# laserbox-muxboard.net
KiCad netlist of a schematic drawn in EAGLE
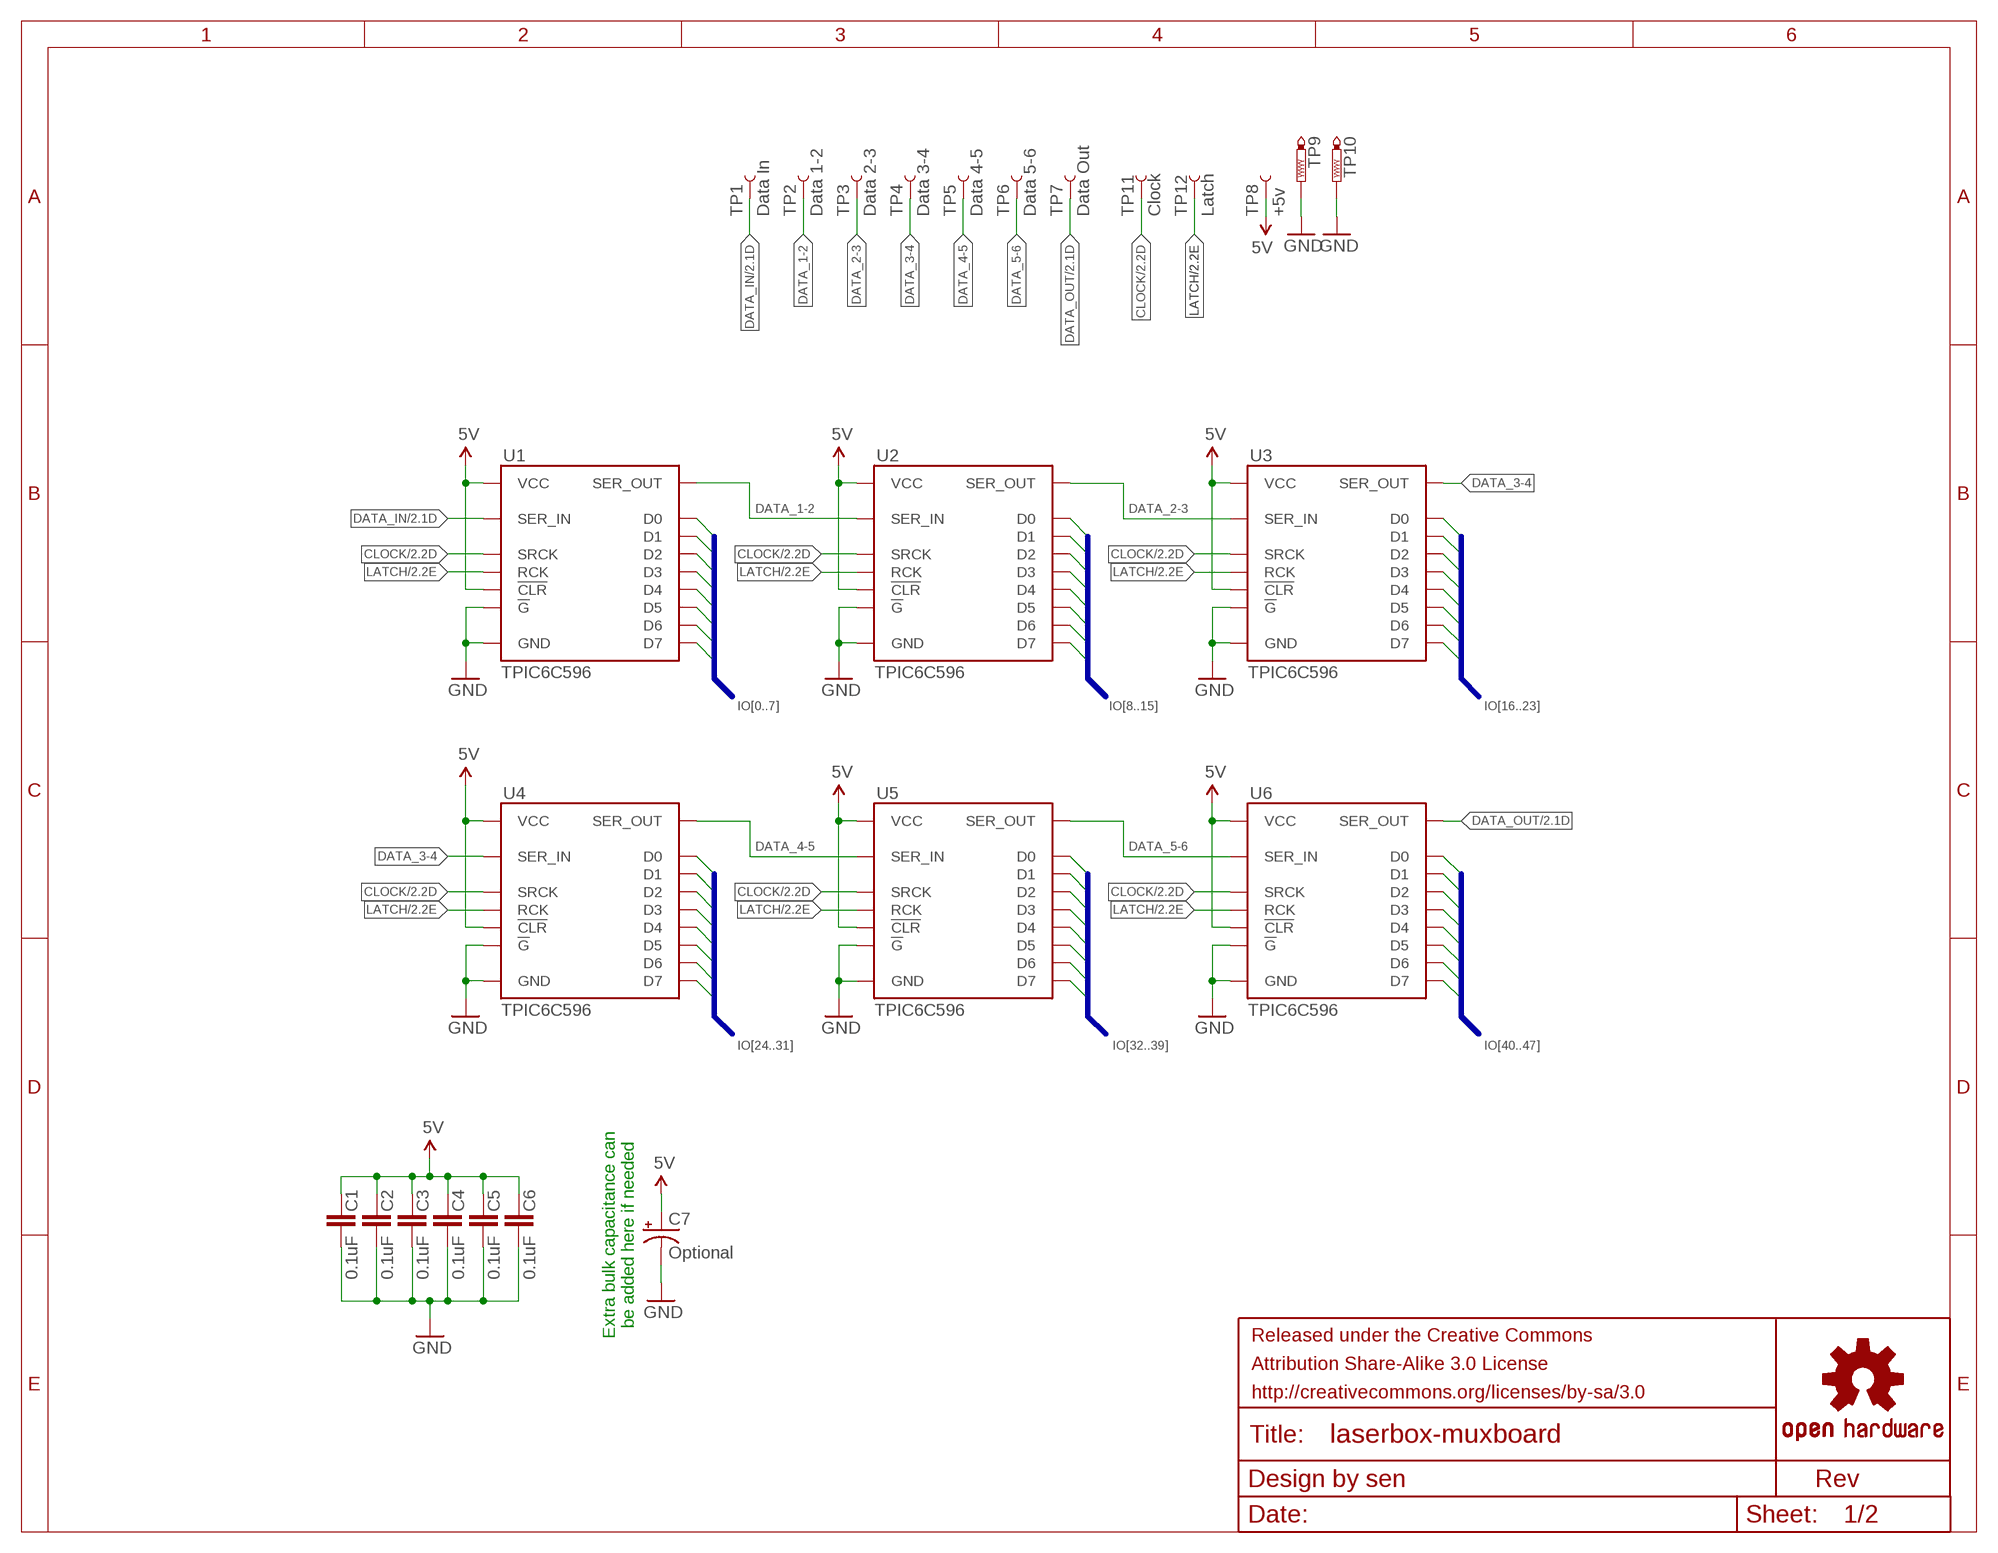
[diagram p0: schematic, sheet 1]
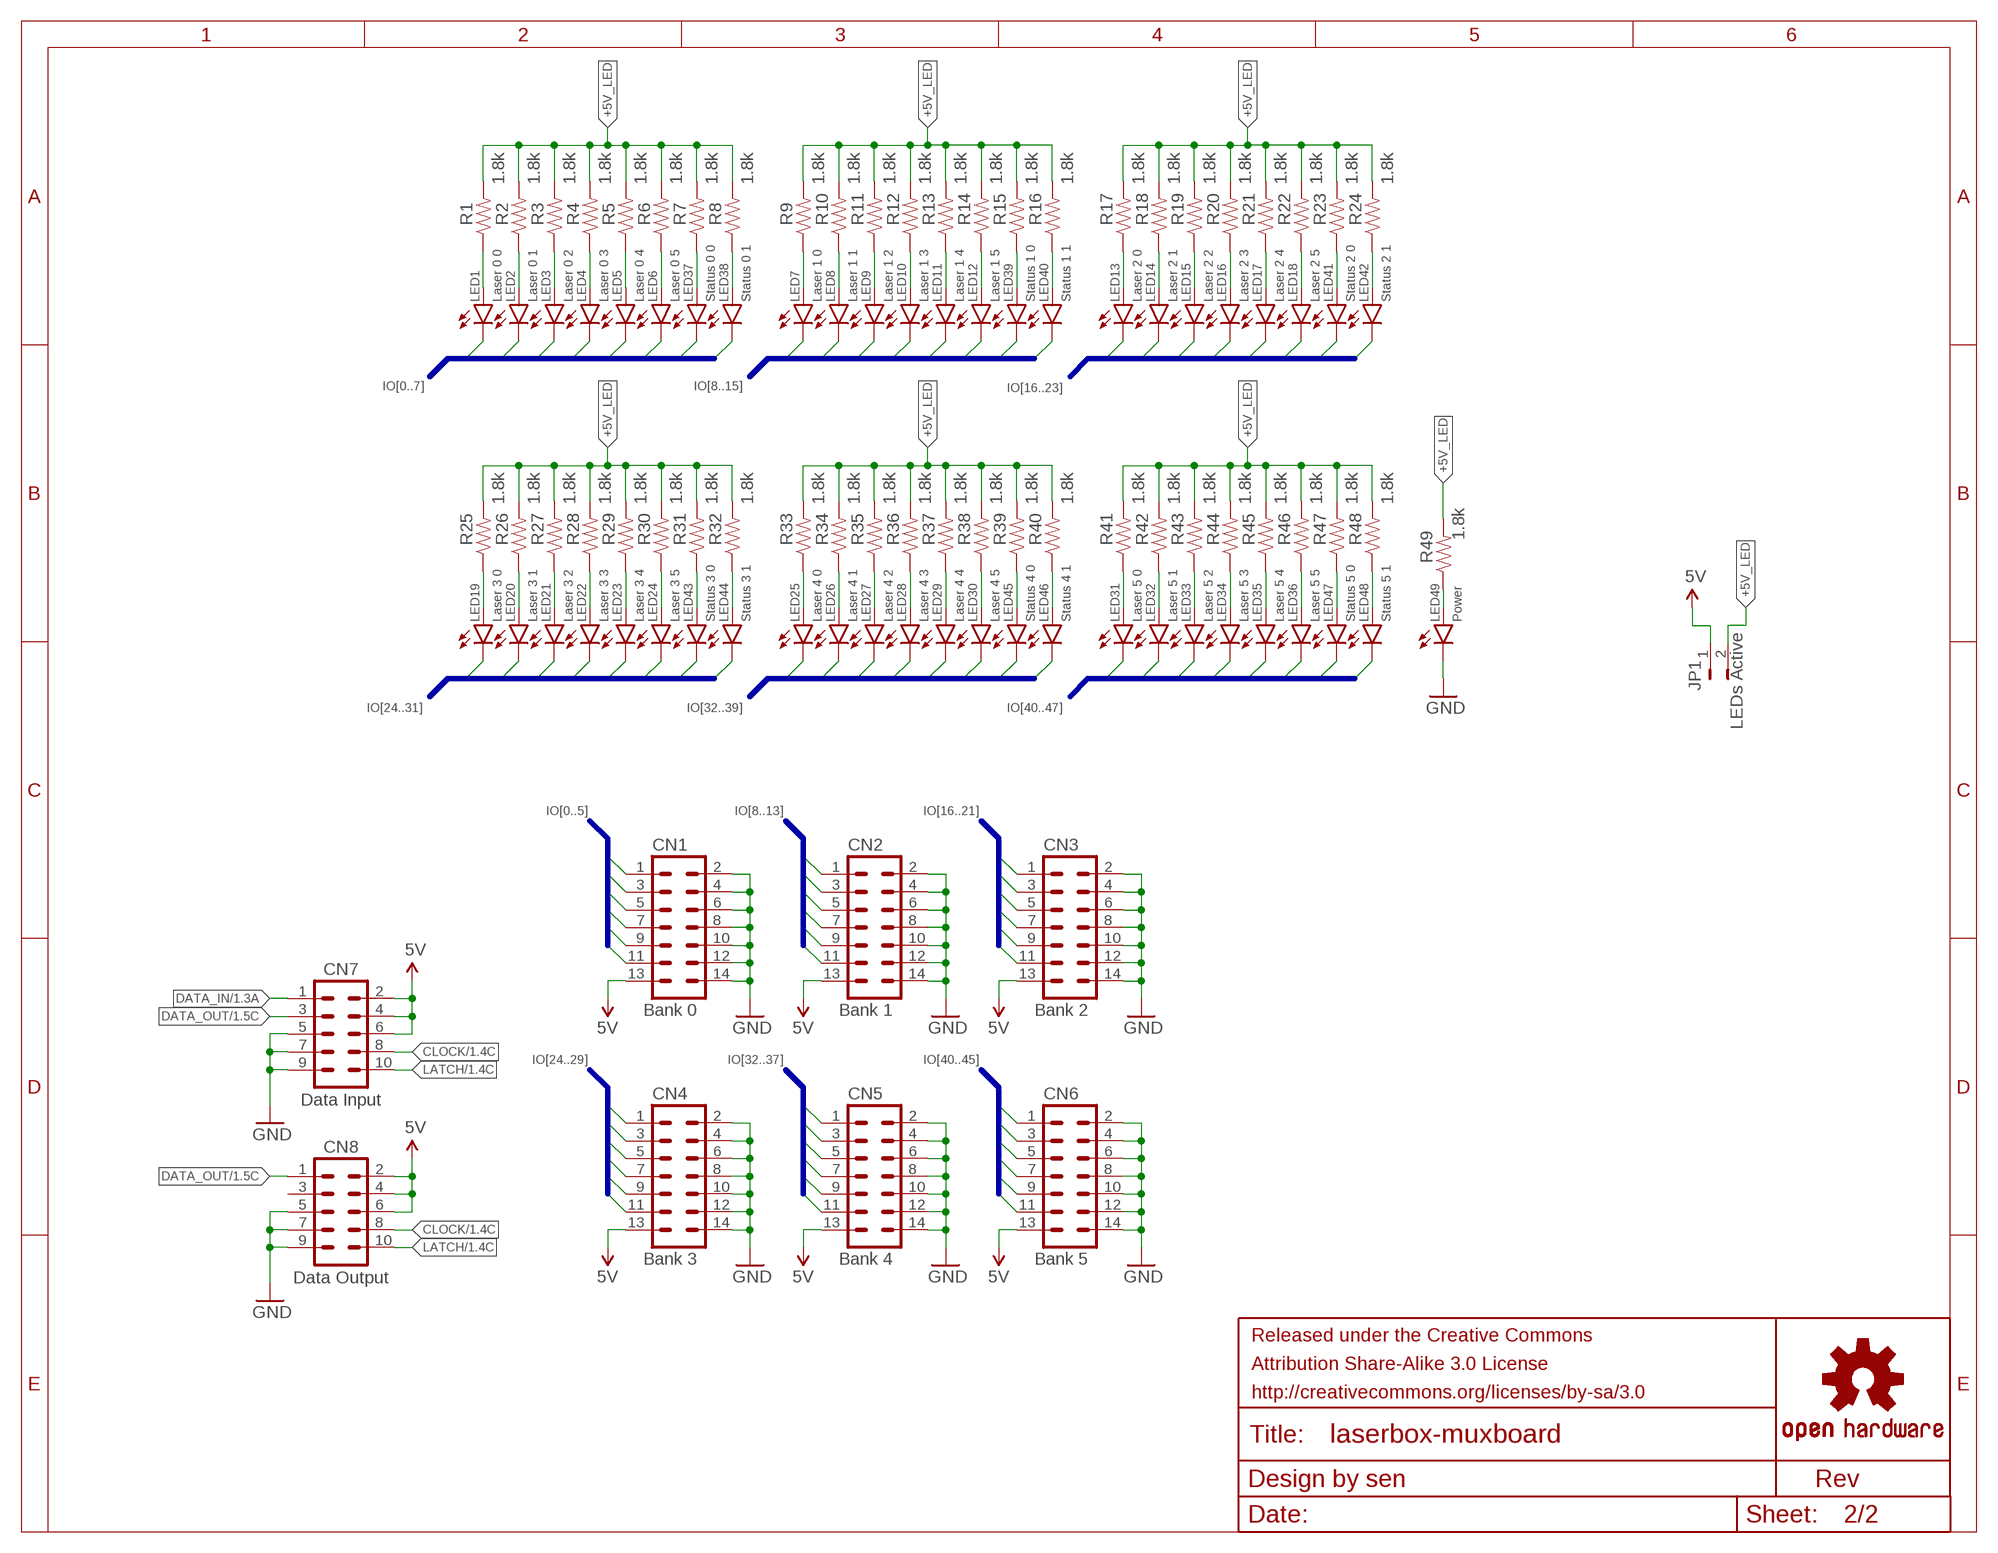
[diagram p1: schematic, sheet 2]

(export (version "E")
  (design (tool "Eeschema 10.0.6"))
  (components
    (comp (ref "C1")
      (value "0.1uF")
      (footprint "eagle-import:0603-CAP")
      (libsource (lib "eagle-import") (part "0.1UF-25V-5%(0603)"))
    )
    (comp (ref "C2")
      (value "0.1uF")
      (footprint "eagle-import:0603-CAP")
      (libsource (lib "eagle-import") (part "0.1UF-25V-5%(0603)"))
    )
    (comp (ref "C3")
      (value "0.1uF")
      (footprint "eagle-import:0603-CAP")
      (libsource (lib "eagle-import") (part "0.1UF-25V-5%(0603)"))
    )
    (comp (ref "C4")
      (value "0.1uF")
      (footprint "eagle-import:0603-CAP")
      (libsource (lib "eagle-import") (part "0.1UF-25V-5%(0603)"))
    )
    (comp (ref "C5")
      (value "0.1uF")
      (footprint "eagle-import:0603-CAP")
      (libsource (lib "eagle-import") (part "0.1UF-25V-5%(0603)"))
    )
    (comp (ref "C6")
      (value "0.1uF")
      (footprint "eagle-import:0603-CAP")
      (libsource (lib "eagle-import") (part "0.1UF-25V-5%(0603)"))
    )
    (comp (ref "C7")
      (value "Optional")
      (footprint "eagle-import:CPOL-RADIAL-10UF-25V")
      (libsource (lib "eagle-import") (part "CAP_POLPTH2"))
    )
    (comp (ref "FRAME1")
      (value "FRAME-LETTER-GRID-OSHW-SENOSHW-LOGO-L")
      (footprint "eagle-import:OSHW-LOGO-L")
      (fields (field (name "REV") "001"))
      (libsource (lib "eagle-import") (part "FRAME-LETTER-GRID-OSHW-SENOSHW-LOGO-L"))
    )
    (comp (ref "TP1")
      (value "Data In")
      (footprint "eagle-import:PAD.03X.05")
      (libsource (lib "eagle-import") (part "TEST-POINT3X5"))
    )
    (comp (ref "TP2")
      (value "Data 1-2")
      (footprint "eagle-import:PAD.03X.05")
      (libsource (lib "eagle-import") (part "TEST-POINT3X5"))
    )
    (comp (ref "TP3")
      (value "Data 2-3")
      (footprint "eagle-import:PAD.03X.05")
      (libsource (lib "eagle-import") (part "TEST-POINT3X5"))
    )
    (comp (ref "TP4")
      (value "Data 3-4")
      (footprint "eagle-import:PAD.03X.05")
      (libsource (lib "eagle-import") (part "TEST-POINT3X5"))
    )
    (comp (ref "TP5")
      (value "Data 4-5")
      (footprint "eagle-import:PAD.03X.05")
      (libsource (lib "eagle-import") (part "TEST-POINT3X5"))
    )
    (comp (ref "TP6")
      (value "Data 5-6")
      (footprint "eagle-import:PAD.03X.05")
      (libsource (lib "eagle-import") (part "TEST-POINT3X5"))
    )
    (comp (ref "TP7")
      (value "Data Out")
      (footprint "eagle-import:PAD.03X.05")
      (libsource (lib "eagle-import") (part "TEST-POINT3X5"))
    )
    (comp (ref "TP8")
      (value "+5v")
      (footprint "eagle-import:PAD.03X.05")
      (libsource (lib "eagle-import") (part "TEST-POINT3X5"))
    )
    (comp (ref "TP9")
      (value "GND")
      (footprint "eagle-import:P1-13")
      (libsource (lib "eagle-import") (part "PTR1PAD1-13"))
    )
    (comp (ref "TP10")
      (value "GND")
      (footprint "eagle-import:P1-13")
      (libsource (lib "eagle-import") (part "PTR1PAD1-13"))
    )
    (comp (ref "TP11")
      (value "Clock")
      (footprint "eagle-import:PAD.03X.05")
      (libsource (lib "eagle-import") (part "TEST-POINT3X5"))
    )
    (comp (ref "TP12")
      (value "Latch")
      (footprint "eagle-import:PAD.03X.05")
      (libsource (lib "eagle-import") (part "TEST-POINT3X5"))
    )
    (comp (ref "U1")
      (value "TPIC6C596")
      (footprint "eagle-import:SO016")
      (libsource (lib "eagle-import") (part "TPIC6C596SOIC"))
    )
    (comp (ref "U2")
      (value "TPIC6C596")
      (footprint "eagle-import:SO016")
      (libsource (lib "eagle-import") (part "TPIC6C596SOIC"))
    )
    (comp (ref "U3")
      (value "TPIC6C596")
      (footprint "eagle-import:SO016")
      (libsource (lib "eagle-import") (part "TPIC6C596SOIC"))
    )
    (comp (ref "U4")
      (value "TPIC6C596")
      (footprint "eagle-import:SO016")
      (libsource (lib "eagle-import") (part "TPIC6C596SOIC"))
    )
    (comp (ref "U5")
      (value "TPIC6C596")
      (footprint "eagle-import:SO016")
      (libsource (lib "eagle-import") (part "TPIC6C596SOIC"))
    )
    (comp (ref "U6")
      (value "TPIC6C596")
      (footprint "eagle-import:SO016")
      (libsource (lib "eagle-import") (part "TPIC6C596SOIC"))
    )
    (comp (ref "CN1")
      (value "Bank 0")
      (footprint "eagle-import:2X7-SHROUDED_LOCK")
      (libsource (lib "eagle-import") (part "M07X2"))
    )
    (comp (ref "CN2")
      (value "Bank 1")
      (footprint "eagle-import:2X7-SHROUDED_LOCK")
      (libsource (lib "eagle-import") (part "M07X2"))
    )
    (comp (ref "CN3")
      (value "Bank 2")
      (footprint "eagle-import:2X7-SHROUDED_LOCK")
      (libsource (lib "eagle-import") (part "M07X2"))
    )
    (comp (ref "CN4")
      (value "Bank 3")
      (footprint "eagle-import:2X7-SHROUDED_LOCK")
      (libsource (lib "eagle-import") (part "M07X2"))
    )
    (comp (ref "CN5")
      (value "Bank 4")
      (footprint "eagle-import:2X7-SHROUDED_LOCK")
      (libsource (lib "eagle-import") (part "M07X2"))
    )
    (comp (ref "CN6")
      (value "Bank 5")
      (footprint "eagle-import:2X7-SHROUDED_LOCK")
      (libsource (lib "eagle-import") (part "M07X2"))
    )
    (comp (ref "CN7")
      (value "Data Input")
      (footprint "eagle-import:2X5-SHROUDED_LOCK")
      (libsource (lib "eagle-import") (part "M05X2SHD_LOCK"))
    )
    (comp (ref "CN8")
      (value "Data Output")
      (footprint "eagle-import:2X5-SHROUDED_LOCK")
      (libsource (lib "eagle-import") (part "M05X2SHD_LOCK"))
    )
    (comp (ref "FRAME2")
      (value "FRAME-LETTER-GRID-OSHW-SENOSHW-LOGO-L")
      (footprint "eagle-import:OSHW-LOGO-L")
      (fields (field (name "REV") "001"))
      (libsource (lib "eagle-import") (part "FRAME-LETTER-GRID-OSHW-SENOSHW-LOGO-L"))
    )
    (comp (ref "JP1")
      (value "LEDs Active")
      (footprint "eagle-import:PTH-JUMPER-2-NO_NO_SILK")
      (libsource (lib "eagle-import") (part "JUMPER-PTH-2-NO"))
    )
    (comp (ref "LED1")
      (value "Laser 0 0")
      (footprint "eagle-import:LED3MM")
      (libsource (lib "eagle-import") (part "LED3MM"))
    )
    (comp (ref "LED2")
      (value "Laser 0 1")
      (footprint "eagle-import:LED3MM")
      (libsource (lib "eagle-import") (part "LED3MM"))
    )
    (comp (ref "LED3")
      (value "Laser 0 2")
      (footprint "eagle-import:LED3MM")
      (libsource (lib "eagle-import") (part "LED3MM"))
    )
    (comp (ref "LED4")
      (value "Laser 0 3")
      (footprint "eagle-import:LED3MM")
      (libsource (lib "eagle-import") (part "LED3MM"))
    )
    (comp (ref "LED5")
      (value "Laser 0 4")
      (footprint "eagle-import:LED3MM")
      (libsource (lib "eagle-import") (part "LED3MM"))
    )
    (comp (ref "LED6")
      (value "Laser 0 5")
      (footprint "eagle-import:LED3MM")
      (libsource (lib "eagle-import") (part "LED3MM"))
    )
    (comp (ref "LED7")
      (value "Laser 1 0")
      (footprint "eagle-import:LED3MM")
      (libsource (lib "eagle-import") (part "LED3MM"))
    )
    (comp (ref "LED8")
      (value "Laser 1 1")
      (footprint "eagle-import:LED3MM")
      (libsource (lib "eagle-import") (part "LED3MM"))
    )
    (comp (ref "LED9")
      (value "Laser 1 2")
      (footprint "eagle-import:LED3MM")
      (libsource (lib "eagle-import") (part "LED3MM"))
    )
    (comp (ref "LED10")
      (value "Laser 1 3")
      (footprint "eagle-import:LED3MM")
      (libsource (lib "eagle-import") (part "LED3MM"))
    )
    (comp (ref "LED11")
      (value "Laser 1 4")
      (footprint "eagle-import:LED3MM")
      (libsource (lib "eagle-import") (part "LED3MM"))
    )
    (comp (ref "LED12")
      (value "Laser 1 5")
      (footprint "eagle-import:LED3MM")
      (libsource (lib "eagle-import") (part "LED3MM"))
    )
    (comp (ref "LED13")
      (value "Laser 2 0")
      (footprint "eagle-import:LED3MM")
      (libsource (lib "eagle-import") (part "LED3MM"))
    )
    (comp (ref "LED14")
      (value "Laser 2 1")
      (footprint "eagle-import:LED3MM")
      (libsource (lib "eagle-import") (part "LED3MM"))
    )
    (comp (ref "LED15")
      (value "Laser 2 2")
      (footprint "eagle-import:LED3MM")
      (libsource (lib "eagle-import") (part "LED3MM"))
    )
    (comp (ref "LED16")
      (value "Laser 2 3")
      (footprint "eagle-import:LED3MM")
      (libsource (lib "eagle-import") (part "LED3MM"))
    )
    (comp (ref "LED17")
      (value "Laser 2 4")
      (footprint "eagle-import:LED3MM")
      (libsource (lib "eagle-import") (part "LED3MM"))
    )
    (comp (ref "LED18")
      (value "Laser 2 5")
      (footprint "eagle-import:LED3MM")
      (libsource (lib "eagle-import") (part "LED3MM"))
    )
    (comp (ref "LED19")
      (value "Laser 3 0")
      (footprint "eagle-import:LED3MM")
      (libsource (lib "eagle-import") (part "LED3MM"))
    )
    (comp (ref "LED20")
      (value "Laser 3 1")
      (footprint "eagle-import:LED3MM")
      (libsource (lib "eagle-import") (part "LED3MM"))
    )
    (comp (ref "LED21")
      (value "Laser 3 2")
      (footprint "eagle-import:LED3MM")
      (libsource (lib "eagle-import") (part "LED3MM"))
    )
    (comp (ref "LED22")
      (value "Laser 3 3")
      (footprint "eagle-import:LED3MM")
      (libsource (lib "eagle-import") (part "LED3MM"))
    )
    (comp (ref "LED23")
      (value "Laser 3 4")
      (footprint "eagle-import:LED3MM")
      (libsource (lib "eagle-import") (part "LED3MM"))
    )
    (comp (ref "LED24")
      (value "Laser 3 5")
      (footprint "eagle-import:LED3MM")
      (libsource (lib "eagle-import") (part "LED3MM"))
    )
    (comp (ref "LED25")
      (value "Laser 4 0")
      (footprint "eagle-import:LED3MM")
      (libsource (lib "eagle-import") (part "LED3MM"))
    )
    (comp (ref "LED26")
      (value "Laser 4 1")
      (footprint "eagle-import:LED3MM")
      (libsource (lib "eagle-import") (part "LED3MM"))
    )
    (comp (ref "LED27")
      (value "Laser 4 2")
      (footprint "eagle-import:LED3MM")
      (libsource (lib "eagle-import") (part "LED3MM"))
    )
    (comp (ref "LED28")
      (value "Laser 4 3")
      (footprint "eagle-import:LED3MM")
      (libsource (lib "eagle-import") (part "LED3MM"))
    )
    (comp (ref "LED29")
      (value "Laser 4 4")
      (footprint "eagle-import:LED3MM")
      (libsource (lib "eagle-import") (part "LED3MM"))
    )
    (comp (ref "LED30")
      (value "Laser 4 5")
      (footprint "eagle-import:LED3MM")
      (libsource (lib "eagle-import") (part "LED3MM"))
    )
    (comp (ref "LED31")
      (value "Laser 5 0")
      (footprint "eagle-import:LED3MM")
      (libsource (lib "eagle-import") (part "LED3MM"))
    )
    (comp (ref "LED32")
      (value "Laser 5 1")
      (footprint "eagle-import:LED3MM")
      (libsource (lib "eagle-import") (part "LED3MM"))
    )
    (comp (ref "LED33")
      (value "Laser 5 2")
      (footprint "eagle-import:LED3MM")
      (libsource (lib "eagle-import") (part "LED3MM"))
    )
    (comp (ref "LED34")
      (value "Laser 5 3")
      (footprint "eagle-import:LED3MM")
      (libsource (lib "eagle-import") (part "LED3MM"))
    )
    (comp (ref "LED35")
      (value "Laser 5 4")
      (footprint "eagle-import:LED3MM")
      (libsource (lib "eagle-import") (part "LED3MM"))
    )
    (comp (ref "LED36")
      (value "Laser 5 5")
      (footprint "eagle-import:LED3MM")
      (libsource (lib "eagle-import") (part "LED3MM"))
    )
    (comp (ref "LED37")
      (value "Status 0 0")
      (footprint "eagle-import:LED3MM")
      (libsource (lib "eagle-import") (part "LED3MM"))
    )
    (comp (ref "LED38")
      (value "Status 0 1")
      (footprint "eagle-import:LED3MM")
      (libsource (lib "eagle-import") (part "LED3MM"))
    )
    (comp (ref "LED39")
      (value "Status 1 0")
      (footprint "eagle-import:LED3MM")
      (libsource (lib "eagle-import") (part "LED3MM"))
    )
    (comp (ref "LED40")
      (value "Status 1 1")
      (footprint "eagle-import:LED3MM")
      (libsource (lib "eagle-import") (part "LED3MM"))
    )
    (comp (ref "LED41")
      (value "Status 2 0")
      (footprint "eagle-import:LED3MM")
      (libsource (lib "eagle-import") (part "LED3MM"))
    )
    (comp (ref "LED42")
      (value "Status 2 1")
      (footprint "eagle-import:LED3MM")
      (libsource (lib "eagle-import") (part "LED3MM"))
    )
    (comp (ref "LED43")
      (value "Status 3 0")
      (footprint "eagle-import:LED3MM")
      (libsource (lib "eagle-import") (part "LED3MM"))
    )
    (comp (ref "LED44")
      (value "Status 3 1")
      (footprint "eagle-import:LED3MM")
      (libsource (lib "eagle-import") (part "LED3MM"))
    )
    (comp (ref "LED45")
      (value "Status 4 0")
      (footprint "eagle-import:LED3MM")
      (libsource (lib "eagle-import") (part "LED3MM"))
    )
    (comp (ref "LED46")
      (value "Status 4 1")
      (footprint "eagle-import:LED3MM")
      (libsource (lib "eagle-import") (part "LED3MM"))
    )
    (comp (ref "LED47")
      (value "Status 5 0")
      (footprint "eagle-import:LED3MM")
      (libsource (lib "eagle-import") (part "LED3MM"))
    )
    (comp (ref "LED48")
      (value "Status 5 1")
      (footprint "eagle-import:LED3MM")
      (libsource (lib "eagle-import") (part "LED3MM"))
    )
    (comp (ref "LED49")
      (value "Power")
      (footprint "eagle-import:LED3MM")
      (libsource (lib "eagle-import") (part "LED3MM"))
    )
    (comp (ref "R1")
      (value "1.8k")
      (footprint "eagle-import:0603-RES")
      (libsource (lib "eagle-import") (part "RESISTOR0603"))
    )
    (comp (ref "R2")
      (value "1.8k")
      (footprint "eagle-import:0603-RES")
      (libsource (lib "eagle-import") (part "RESISTOR0603"))
    )
    (comp (ref "R3")
      (value "1.8k")
      (footprint "eagle-import:0603-RES")
      (libsource (lib "eagle-import") (part "RESISTOR0603"))
    )
    (comp (ref "R4")
      (value "1.8k")
      (footprint "eagle-import:0603-RES")
      (libsource (lib "eagle-import") (part "RESISTOR0603"))
    )
    (comp (ref "R5")
      (value "1.8k")
      (footprint "eagle-import:0603-RES")
      (libsource (lib "eagle-import") (part "RESISTOR0603"))
    )
    (comp (ref "R6")
      (value "1.8k")
      (footprint "eagle-import:0603-RES")
      (libsource (lib "eagle-import") (part "RESISTOR0603"))
    )
    (comp (ref "R7")
      (value "1.8k")
      (footprint "eagle-import:0603-RES")
      (libsource (lib "eagle-import") (part "RESISTOR0603"))
    )
    (comp (ref "R8")
      (value "1.8k")
      (footprint "eagle-import:0603-RES")
      (libsource (lib "eagle-import") (part "RESISTOR0603"))
    )
    (comp (ref "R9")
      (value "1.8k")
      (footprint "eagle-import:0603-RES")
      (libsource (lib "eagle-import") (part "RESISTOR0603"))
    )
    (comp (ref "R10")
      (value "1.8k")
      (footprint "eagle-import:0603-RES")
      (libsource (lib "eagle-import") (part "RESISTOR0603"))
    )
    (comp (ref "R11")
      (value "1.8k")
      (footprint "eagle-import:0603-RES")
      (libsource (lib "eagle-import") (part "RESISTOR0603"))
    )
    (comp (ref "R12")
      (value "1.8k")
      (footprint "eagle-import:0603-RES")
      (libsource (lib "eagle-import") (part "RESISTOR0603"))
    )
    (comp (ref "R13")
      (value "1.8k")
      (footprint "eagle-import:0603-RES")
      (libsource (lib "eagle-import") (part "RESISTOR0603"))
    )
    (comp (ref "R14")
      (value "1.8k")
      (footprint "eagle-import:0603-RES")
      (libsource (lib "eagle-import") (part "RESISTOR0603"))
    )
    (comp (ref "R15")
      (value "1.8k")
      (footprint "eagle-import:0603-RES")
      (libsource (lib "eagle-import") (part "RESISTOR0603"))
    )
    (comp (ref "R16")
      (value "1.8k")
      (footprint "eagle-import:0603-RES")
      (libsource (lib "eagle-import") (part "RESISTOR0603"))
    )
    (comp (ref "R17")
      (value "1.8k")
      (footprint "eagle-import:0603-RES")
      (libsource (lib "eagle-import") (part "RESISTOR0603"))
    )
    (comp (ref "R18")
      (value "1.8k")
      (footprint "eagle-import:0603-RES")
      (libsource (lib "eagle-import") (part "RESISTOR0603"))
    )
    (comp (ref "R19")
      (value "1.8k")
      (footprint "eagle-import:0603-RES")
      (libsource (lib "eagle-import") (part "RESISTOR0603"))
    )
    (comp (ref "R20")
      (value "1.8k")
      (footprint "eagle-import:0603-RES")
      (libsource (lib "eagle-import") (part "RESISTOR0603"))
    )
    (comp (ref "R21")
      (value "1.8k")
      (footprint "eagle-import:0603-RES")
      (libsource (lib "eagle-import") (part "RESISTOR0603"))
    )
    (comp (ref "R22")
      (value "1.8k")
      (footprint "eagle-import:0603-RES")
      (libsource (lib "eagle-import") (part "RESISTOR0603"))
    )
    (comp (ref "R23")
      (value "1.8k")
      (footprint "eagle-import:0603-RES")
      (libsource (lib "eagle-import") (part "RESISTOR0603"))
    )
    (comp (ref "R24")
      (value "1.8k")
      (footprint "eagle-import:0603-RES")
      (libsource (lib "eagle-import") (part "RESISTOR0603"))
    )
    (comp (ref "R25")
      (value "1.8k")
      (footprint "eagle-import:0603-RES")
      (libsource (lib "eagle-import") (part "RESISTOR0603"))
    )
    (comp (ref "R26")
      (value "1.8k")
      (footprint "eagle-import:0603-RES")
      (libsource (lib "eagle-import") (part "RESISTOR0603"))
    )
    (comp (ref "R27")
      (value "1.8k")
      (footprint "eagle-import:0603-RES")
      (libsource (lib "eagle-import") (part "RESISTOR0603"))
    )
    (comp (ref "R28")
      (value "1.8k")
      (footprint "eagle-import:0603-RES")
      (libsource (lib "eagle-import") (part "RESISTOR0603"))
    )
    (comp (ref "R29")
      (value "1.8k")
      (footprint "eagle-import:0603-RES")
      (libsource (lib "eagle-import") (part "RESISTOR0603"))
    )
    (comp (ref "R30")
      (value "1.8k")
      (footprint "eagle-import:0603-RES")
      (libsource (lib "eagle-import") (part "RESISTOR0603"))
    )
    (comp (ref "R31")
      (value "1.8k")
      (footprint "eagle-import:0603-RES")
      (libsource (lib "eagle-import") (part "RESISTOR0603"))
    )
    (comp (ref "R32")
      (value "1.8k")
      (footprint "eagle-import:0603-RES")
      (libsource (lib "eagle-import") (part "RESISTOR0603"))
    )
    (comp (ref "R33")
      (value "1.8k")
      (footprint "eagle-import:0603-RES")
      (libsource (lib "eagle-import") (part "RESISTOR0603"))
    )
    (comp (ref "R34")
      (value "1.8k")
      (footprint "eagle-import:0603-RES")
      (libsource (lib "eagle-import") (part "RESISTOR0603"))
    )
    (comp (ref "R35")
      (value "1.8k")
      (footprint "eagle-import:0603-RES")
      (libsource (lib "eagle-import") (part "RESISTOR0603"))
    )
    (comp (ref "R36")
      (value "1.8k")
      (footprint "eagle-import:0603-RES")
      (libsource (lib "eagle-import") (part "RESISTOR0603"))
    )
    (comp (ref "R37")
      (value "1.8k")
      (footprint "eagle-import:0603-RES")
      (libsource (lib "eagle-import") (part "RESISTOR0603"))
    )
    (comp (ref "R38")
      (value "1.8k")
      (footprint "eagle-import:0603-RES")
      (libsource (lib "eagle-import") (part "RESISTOR0603"))
    )
    (comp (ref "R39")
      (value "1.8k")
      (footprint "eagle-import:0603-RES")
      (libsource (lib "eagle-import") (part "RESISTOR0603"))
    )
    (comp (ref "R40")
      (value "1.8k")
      (footprint "eagle-import:0603-RES")
      (libsource (lib "eagle-import") (part "RESISTOR0603"))
    )
    (comp (ref "R41")
      (value "1.8k")
      (footprint "eagle-import:0603-RES")
      (libsource (lib "eagle-import") (part "RESISTOR0603"))
    )
    (comp (ref "R42")
      (value "1.8k")
      (footprint "eagle-import:0603-RES")
      (libsource (lib "eagle-import") (part "RESISTOR0603"))
    )
    (comp (ref "R43")
      (value "1.8k")
      (footprint "eagle-import:0603-RES")
      (libsource (lib "eagle-import") (part "RESISTOR0603"))
    )
    (comp (ref "R44")
      (value "1.8k")
      (footprint "eagle-import:0603-RES")
      (libsource (lib "eagle-import") (part "RESISTOR0603"))
    )
    (comp (ref "R45")
      (value "1.8k")
      (footprint "eagle-import:0603-RES")
      (libsource (lib "eagle-import") (part "RESISTOR0603"))
    )
    (comp (ref "R46")
      (value "1.8k")
      (footprint "eagle-import:0603-RES")
      (libsource (lib "eagle-import") (part "RESISTOR0603"))
    )
    (comp (ref "R47")
      (value "1.8k")
      (footprint "eagle-import:0603-RES")
      (libsource (lib "eagle-import") (part "RESISTOR0603"))
    )
    (comp (ref "R48")
      (value "1.8k")
      (footprint "eagle-import:0603-RES")
      (libsource (lib "eagle-import") (part "RESISTOR0603"))
    )
    (comp (ref "R49")
      (value "1.8k")
      (footprint "eagle-import:0603-RES")
      (libsource (lib "eagle-import") (part "RESISTOR0603"))
    )
  )
  (nets
    (net (code "1") (name "+5V_LED") (class "Default")
      (node (ref "JP1") (pin "2") (pinfunction "2_2") (pintype "passive"))
      (node (ref "R1") (pin "2") (pinfunction "2_2") (pintype "passive"))
      (node (ref "R10") (pin "2") (pinfunction "2_2") (pintype "passive"))
      (node (ref "R11") (pin "2") (pinfunction "2_2") (pintype "passive"))
      (node (ref "R12") (pin "2") (pinfunction "2_2") (pintype "passive"))
      (node (ref "R13") (pin "2") (pinfunction "2_2") (pintype "passive"))
      (node (ref "R14") (pin "2") (pinfunction "2_2") (pintype "passive"))
      (node (ref "R15") (pin "2") (pinfunction "2_2") (pintype "passive"))
      (node (ref "R16") (pin "2") (pinfunction "2_2") (pintype "passive"))
      (node (ref "R17") (pin "2") (pinfunction "2_2") (pintype "passive"))
      (node (ref "R18") (pin "2") (pinfunction "2_2") (pintype "passive"))
      (node (ref "R19") (pin "2") (pinfunction "2_2") (pintype "passive"))
      (node (ref "R2") (pin "2") (pinfunction "2_2") (pintype "passive"))
      (node (ref "R20") (pin "2") (pinfunction "2_2") (pintype "passive"))
      (node (ref "R21") (pin "2") (pinfunction "2_2") (pintype "passive"))
      (node (ref "R22") (pin "2") (pinfunction "2_2") (pintype "passive"))
      (node (ref "R23") (pin "2") (pinfunction "2_2") (pintype "passive"))
      (node (ref "R24") (pin "2") (pinfunction "2_2") (pintype "passive"))
      (node (ref "R25") (pin "2") (pinfunction "2_2") (pintype "passive"))
      (node (ref "R26") (pin "2") (pinfunction "2_2") (pintype "passive"))
      (node (ref "R27") (pin "2") (pinfunction "2_2") (pintype "passive"))
      (node (ref "R28") (pin "2") (pinfunction "2_2") (pintype "passive"))
      (node (ref "R29") (pin "2") (pinfunction "2_2") (pintype "passive"))
      (node (ref "R3") (pin "2") (pinfunction "2_2") (pintype "passive"))
      (node (ref "R30") (pin "2") (pinfunction "2_2") (pintype "passive"))
      (node (ref "R31") (pin "2") (pinfunction "2_2") (pintype "passive"))
      (node (ref "R32") (pin "2") (pinfunction "2_2") (pintype "passive"))
      (node (ref "R33") (pin "2") (pinfunction "2_2") (pintype "passive"))
      (node (ref "R34") (pin "2") (pinfunction "2_2") (pintype "passive"))
      (node (ref "R35") (pin "2") (pinfunction "2_2") (pintype "passive"))
      (node (ref "R36") (pin "2") (pinfunction "2_2") (pintype "passive"))
      (node (ref "R37") (pin "2") (pinfunction "2_2") (pintype "passive"))
      (node (ref "R38") (pin "2") (pinfunction "2_2") (pintype "passive"))
      (node (ref "R39") (pin "2") (pinfunction "2_2") (pintype "passive"))
      (node (ref "R4") (pin "2") (pinfunction "2_2") (pintype "passive"))
      (node (ref "R40") (pin "2") (pinfunction "2_2") (pintype "passive"))
      (node (ref "R41") (pin "2") (pinfunction "2_2") (pintype "passive"))
      (node (ref "R42") (pin "2") (pinfunction "2_2") (pintype "passive"))
      (node (ref "R43") (pin "2") (pinfunction "2_2") (pintype "passive"))
      (node (ref "R44") (pin "2") (pinfunction "2_2") (pintype "passive"))
      (node (ref "R45") (pin "2") (pinfunction "2_2") (pintype "passive"))
      (node (ref "R46") (pin "2") (pinfunction "2_2") (pintype "passive"))
      (node (ref "R47") (pin "2") (pinfunction "2_2") (pintype "passive"))
      (node (ref "R48") (pin "2") (pinfunction "2_2") (pintype "passive"))
      (node (ref "R49") (pin "2") (pinfunction "2_2") (pintype "passive"))
      (node (ref "R5") (pin "2") (pinfunction "2_2") (pintype "passive"))
      (node (ref "R6") (pin "2") (pinfunction "2_2") (pintype "passive"))
      (node (ref "R7") (pin "2") (pinfunction "2_2") (pintype "passive"))
      (node (ref "R8") (pin "2") (pinfunction "2_2") (pintype "passive"))
      (node (ref "R9") (pin "2") (pinfunction "2_2") (pintype "passive"))
    )
    (net (code "20") (name "5V") (class "Default")
      (node (ref "C1") (pin "1") (pinfunction "1_1") (pintype "passive"))
      (node (ref "C2") (pin "1") (pinfunction "1_1") (pintype "passive"))
      (node (ref "C3") (pin "1") (pinfunction "1_1") (pintype "passive"))
      (node (ref "C4") (pin "1") (pinfunction "1_1") (pintype "passive"))
      (node (ref "C5") (pin "1") (pinfunction "1_1") (pintype "passive"))
      (node (ref "C6") (pin "1") (pinfunction "1_1") (pintype "passive"))
      (node (ref "C7") (pin "1") (pinfunction "+_1") (pintype "passive"))
      (node (ref "CN1") (pin "13") (pinfunction "13_13") (pintype "passive"))
      (node (ref "CN2") (pin "13") (pinfunction "13_13") (pintype "passive"))
      (node (ref "CN3") (pin "13") (pinfunction "13_13") (pintype "passive"))
      (node (ref "CN4") (pin "13") (pinfunction "13_13") (pintype "passive"))
      (node (ref "CN5") (pin "13") (pinfunction "13_13") (pintype "passive"))
      (node (ref "CN6") (pin "13") (pinfunction "13_13") (pintype "passive"))
      (node (ref "CN7") (pin "2") (pinfunction "2_2") (pintype "passive"))
      (node (ref "CN7") (pin "4") (pinfunction "4_4") (pintype "passive"))
      (node (ref "CN7") (pin "6") (pinfunction "6_6") (pintype "passive"))
      (node (ref "CN8") (pin "2") (pinfunction "2_2") (pintype "passive"))
      (node (ref "CN8") (pin "4") (pinfunction "4_4") (pintype "passive"))
      (node (ref "CN8") (pin "6") (pinfunction "6_6") (pintype "passive"))
      (node (ref "JP1") (pin "1") (pinfunction "1_1") (pintype "passive"))
      (node (ref "TP8") (pin "P$1") (pinfunction "1_P$1") (pintype "bidirectional"))
      (node (ref "U1") (pin "1") (pinfunction "VCC_1") (pintype "power_in"))
      (node (ref "U1") (pin "7") (pinfunction "~{CLR}_7") (pintype "input"))
      (node (ref "U2") (pin "1") (pinfunction "VCC_1") (pintype "power_in"))
      (node (ref "U2") (pin "7") (pinfunction "~{CLR}_7") (pintype "input"))
      (node (ref "U3") (pin "1") (pinfunction "VCC_1") (pintype "power_in"))
      (node (ref "U3") (pin "7") (pinfunction "~{CLR}_7") (pintype "input"))
      (node (ref "U4") (pin "1") (pinfunction "VCC_1") (pintype "power_in"))
      (node (ref "U4") (pin "7") (pinfunction "~{CLR}_7") (pintype "input"))
      (node (ref "U5") (pin "1") (pinfunction "VCC_1") (pintype "power_in"))
      (node (ref "U5") (pin "7") (pinfunction "~{CLR}_7") (pintype "input"))
      (node (ref "U6") (pin "1") (pinfunction "VCC_1") (pintype "power_in"))
      (node (ref "U6") (pin "7") (pinfunction "~{CLR}_7") (pintype "input"))
    )
    (net (code "21") (name "CLOCK") (class "Default")
      (node (ref "CN7") (pin "8") (pinfunction "8_8") (pintype "passive"))
      (node (ref "CN8") (pin "8") (pinfunction "8_8") (pintype "passive"))
      (node (ref "TP11") (pin "P$1") (pinfunction "1_P$1") (pintype "bidirectional"))
      (node (ref "U1") (pin "15") (pinfunction "SRCK_15") (pintype "input"))
      (node (ref "U2") (pin "15") (pinfunction "SRCK_15") (pintype "input"))
      (node (ref "U3") (pin "15") (pinfunction "SRCK_15") (pintype "input"))
      (node (ref "U4") (pin "15") (pinfunction "SRCK_15") (pintype "input"))
      (node (ref "U5") (pin "15") (pinfunction "SRCK_15") (pintype "input"))
      (node (ref "U6") (pin "15") (pinfunction "SRCK_15") (pintype "input"))
    )
    (net (code "22") (name "DATA_1-2") (class "Default")
      (node (ref "TP2") (pin "P$1") (pinfunction "1_P$1") (pintype "bidirectional"))
      (node (ref "U1") (pin "9") (pinfunction "SER_OUT_9") (pintype "output"))
      (node (ref "U2") (pin "2") (pinfunction "SER_IN_2") (pintype "input"))
    )
    (net (code "23") (name "DATA_2-3") (class "Default")
      (node (ref "TP3") (pin "P$1") (pinfunction "1_P$1") (pintype "bidirectional"))
      (node (ref "U2") (pin "9") (pinfunction "SER_OUT_9") (pintype "output"))
      (node (ref "U3") (pin "2") (pinfunction "SER_IN_2") (pintype "input"))
    )
    (net (code "24") (name "DATA_3-4") (class "Default")
      (node (ref "TP4") (pin "P$1") (pinfunction "1_P$1") (pintype "bidirectional"))
      (node (ref "U3") (pin "9") (pinfunction "SER_OUT_9") (pintype "output"))
      (node (ref "U4") (pin "2") (pinfunction "SER_IN_2") (pintype "input"))
    )
    (net (code "25") (name "DATA_4-5") (class "Default")
      (node (ref "TP5") (pin "P$1") (pinfunction "1_P$1") (pintype "bidirectional"))
      (node (ref "U4") (pin "9") (pinfunction "SER_OUT_9") (pintype "output"))
      (node (ref "U5") (pin "2") (pinfunction "SER_IN_2") (pintype "input"))
    )
    (net (code "26") (name "DATA_5-6") (class "Default")
      (node (ref "TP6") (pin "P$1") (pinfunction "1_P$1") (pintype "bidirectional"))
      (node (ref "U5") (pin "9") (pinfunction "SER_OUT_9") (pintype "output"))
      (node (ref "U6") (pin "2") (pinfunction "SER_IN_2") (pintype "input"))
    )
    (net (code "27") (name "DATA_IN") (class "Default")
      (node (ref "CN7") (pin "1") (pinfunction "1_1") (pintype "passive"))
      (node (ref "TP1") (pin "P$1") (pinfunction "1_P$1") (pintype "bidirectional"))
      (node (ref "U1") (pin "2") (pinfunction "SER_IN_2") (pintype "input"))
    )
    (net (code "28") (name "DATA_OUT") (class "Default")
      (node (ref "CN7") (pin "3") (pinfunction "3_3") (pintype "passive"))
      (node (ref "CN8") (pin "1") (pinfunction "1_1") (pintype "passive"))
      (node (ref "TP7") (pin "P$1") (pinfunction "1_P$1") (pintype "bidirectional"))
      (node (ref "U6") (pin "9") (pinfunction "SER_OUT_9") (pintype "output"))
    )
    (net (code "29") (name "GND") (class "Default")
      (node (ref "C1") (pin "2") (pinfunction "2_2") (pintype "passive"))
      (node (ref "C2") (pin "2") (pinfunction "2_2") (pintype "passive"))
      (node (ref "C3") (pin "2") (pinfunction "2_2") (pintype "passive"))
      (node (ref "C4") (pin "2") (pinfunction "2_2") (pintype "passive"))
      (node (ref "C5") (pin "2") (pinfunction "2_2") (pintype "passive"))
      (node (ref "C6") (pin "2") (pinfunction "2_2") (pintype "passive"))
      (node (ref "C7") (pin "2") (pinfunction "-_2") (pintype "passive"))
      (node (ref "CN1") (pin "10") (pinfunction "10_10") (pintype "passive"))
      (node (ref "CN1") (pin "12") (pinfunction "12_12") (pintype "passive"))
      (node (ref "CN1") (pin "14") (pinfunction "14_14") (pintype "passive"))
      (node (ref "CN1") (pin "2") (pinfunction "2_2") (pintype "passive"))
      (node (ref "CN1") (pin "4") (pinfunction "4_4") (pintype "passive"))
      (node (ref "CN1") (pin "6") (pinfunction "6_6") (pintype "passive"))
      (node (ref "CN1") (pin "8") (pinfunction "8_8") (pintype "passive"))
      (node (ref "CN2") (pin "10") (pinfunction "10_10") (pintype "passive"))
      (node (ref "CN2") (pin "12") (pinfunction "12_12") (pintype "passive"))
      (node (ref "CN2") (pin "14") (pinfunction "14_14") (pintype "passive"))
      (node (ref "CN2") (pin "2") (pinfunction "2_2") (pintype "passive"))
      (node (ref "CN2") (pin "4") (pinfunction "4_4") (pintype "passive"))
      (node (ref "CN2") (pin "6") (pinfunction "6_6") (pintype "passive"))
      (node (ref "CN2") (pin "8") (pinfunction "8_8") (pintype "passive"))
      (node (ref "CN3") (pin "10") (pinfunction "10_10") (pintype "passive"))
      (node (ref "CN3") (pin "12") (pinfunction "12_12") (pintype "passive"))
      (node (ref "CN3") (pin "14") (pinfunction "14_14") (pintype "passive"))
      (node (ref "CN3") (pin "2") (pinfunction "2_2") (pintype "passive"))
      (node (ref "CN3") (pin "4") (pinfunction "4_4") (pintype "passive"))
      (node (ref "CN3") (pin "6") (pinfunction "6_6") (pintype "passive"))
      (node (ref "CN3") (pin "8") (pinfunction "8_8") (pintype "passive"))
      (node (ref "CN4") (pin "10") (pinfunction "10_10") (pintype "passive"))
      (node (ref "CN4") (pin "12") (pinfunction "12_12") (pintype "passive"))
      (node (ref "CN4") (pin "14") (pinfunction "14_14") (pintype "passive"))
      (node (ref "CN4") (pin "2") (pinfunction "2_2") (pintype "passive"))
      (node (ref "CN4") (pin "4") (pinfunction "4_4") (pintype "passive"))
      (node (ref "CN4") (pin "6") (pinfunction "6_6") (pintype "passive"))
      (node (ref "CN4") (pin "8") (pinfunction "8_8") (pintype "passive"))
      (node (ref "CN5") (pin "10") (pinfunction "10_10") (pintype "passive"))
      (node (ref "CN5") (pin "12") (pinfunction "12_12") (pintype "passive"))
      (node (ref "CN5") (pin "14") (pinfunction "14_14") (pintype "passive"))
      (node (ref "CN5") (pin "2") (pinfunction "2_2") (pintype "passive"))
      (node (ref "CN5") (pin "4") (pinfunction "4_4") (pintype "passive"))
      (node (ref "CN5") (pin "6") (pinfunction "6_6") (pintype "passive"))
      (node (ref "CN5") (pin "8") (pinfunction "8_8") (pintype "passive"))
      (node (ref "CN6") (pin "10") (pinfunction "10_10") (pintype "passive"))
      (node (ref "CN6") (pin "12") (pinfunction "12_12") (pintype "passive"))
      (node (ref "CN6") (pin "14") (pinfunction "14_14") (pintype "passive"))
      (node (ref "CN6") (pin "2") (pinfunction "2_2") (pintype "passive"))
      (node (ref "CN6") (pin "4") (pinfunction "4_4") (pintype "passive"))
      (node (ref "CN6") (pin "6") (pinfunction "6_6") (pintype "passive"))
      (node (ref "CN6") (pin "8") (pinfunction "8_8") (pintype "passive"))
      (node (ref "CN7") (pin "5") (pinfunction "5_5") (pintype "passive"))
      (node (ref "CN7") (pin "7") (pinfunction "7_7") (pintype "passive"))
      (node (ref "CN7") (pin "9") (pinfunction "9_9") (pintype "passive"))
      (node (ref "CN8") (pin "5") (pinfunction "5_5") (pintype "passive"))
      (node (ref "CN8") (pin "7") (pinfunction "7_7") (pintype "passive"))
      (node (ref "CN8") (pin "9") (pinfunction "9_9") (pintype "passive"))
      (node (ref "LED49") (pin "K") (pinfunction "C_K") (pintype "passive"))
      (node (ref "TP10") (pin "TP") (pinfunction "TP_TP") (pintype "input"))
      (node (ref "TP9") (pin "TP") (pinfunction "TP_TP") (pintype "input"))
      (node (ref "U1") (pin "16") (pinfunction "GND_16") (pintype "power_in"))
      (node (ref "U1") (pin "8") (pinfunction "~{G}_8") (pintype "input"))
      (node (ref "U2") (pin "16") (pinfunction "GND_16") (pintype "power_in"))
      (node (ref "U2") (pin "8") (pinfunction "~{G}_8") (pintype "input"))
      (node (ref "U3") (pin "16") (pinfunction "GND_16") (pintype "power_in"))
      (node (ref "U3") (pin "8") (pinfunction "~{G}_8") (pintype "input"))
      (node (ref "U4") (pin "16") (pinfunction "GND_16") (pintype "power_in"))
      (node (ref "U4") (pin "8") (pinfunction "~{G}_8") (pintype "input"))
      (node (ref "U5") (pin "16") (pinfunction "GND_16") (pintype "power_in"))
      (node (ref "U5") (pin "8") (pinfunction "~{G}_8") (pintype "input"))
      (node (ref "U6") (pin "16") (pinfunction "GND_16") (pintype "power_in"))
      (node (ref "U6") (pin "8") (pinfunction "~{G}_8") (pintype "input"))
    )
    (net (code "30") (name "IO0") (class "Default")
      (node (ref "CN1") (pin "1") (pinfunction "1_1") (pintype "passive"))
      (node (ref "LED1") (pin "K") (pinfunction "C_K") (pintype "passive"))
      (node (ref "U1") (pin "3") (pinfunction "D0_3") (pintype "output"))
    )
    (net (code "31") (name "IO1") (class "Default")
      (node (ref "CN1") (pin "3") (pinfunction "3_3") (pintype "passive"))
      (node (ref "LED2") (pin "K") (pinfunction "C_K") (pintype "passive"))
      (node (ref "U1") (pin "4") (pinfunction "D1_4") (pintype "output"))
    )
    (net (code "32") (name "IO2") (class "Default")
      (node (ref "CN1") (pin "5") (pinfunction "5_5") (pintype "passive"))
      (node (ref "LED3") (pin "K") (pinfunction "C_K") (pintype "passive"))
      (node (ref "U1") (pin "5") (pinfunction "D2_5") (pintype "output"))
    )
    (net (code "33") (name "IO3") (class "Default")
      (node (ref "CN1") (pin "7") (pinfunction "7_7") (pintype "passive"))
      (node (ref "LED4") (pin "K") (pinfunction "C_K") (pintype "passive"))
      (node (ref "U1") (pin "6") (pinfunction "D3_6") (pintype "output"))
    )
    (net (code "34") (name "IO4") (class "Default")
      (node (ref "CN1") (pin "9") (pinfunction "9_9") (pintype "passive"))
      (node (ref "LED5") (pin "K") (pinfunction "C_K") (pintype "passive"))
      (node (ref "U1") (pin "11") (pinfunction "D4_11") (pintype "output"))
    )
    (net (code "35") (name "IO5") (class "Default")
      (node (ref "CN1") (pin "11") (pinfunction "11_11") (pintype "passive"))
      (node (ref "LED6") (pin "K") (pinfunction "C_K") (pintype "passive"))
      (node (ref "U1") (pin "12") (pinfunction "D5_12") (pintype "output"))
    )
    (net (code "36") (name "IO6") (class "Default")
      (node (ref "LED37") (pin "K") (pinfunction "C_K") (pintype "passive"))
      (node (ref "U1") (pin "13") (pinfunction "D6_13") (pintype "output"))
    )
    (net (code "37") (name "IO7") (class "Default")
      (node (ref "LED38") (pin "K") (pinfunction "C_K") (pintype "passive"))
      (node (ref "U1") (pin "14") (pinfunction "D7_14") (pintype "output"))
    )
    (net (code "38") (name "IO8") (class "Default")
      (node (ref "CN2") (pin "1") (pinfunction "1_1") (pintype "passive"))
      (node (ref "LED7") (pin "K") (pinfunction "C_K") (pintype "passive"))
      (node (ref "U2") (pin "3") (pinfunction "D0_3") (pintype "output"))
    )
    (net (code "39") (name "IO9") (class "Default")
      (node (ref "CN2") (pin "3") (pinfunction "3_3") (pintype "passive"))
      (node (ref "LED8") (pin "K") (pinfunction "C_K") (pintype "passive"))
      (node (ref "U2") (pin "4") (pinfunction "D1_4") (pintype "output"))
    )
    (net (code "40") (name "IO10") (class "Default")
      (node (ref "CN2") (pin "5") (pinfunction "5_5") (pintype "passive"))
      (node (ref "LED9") (pin "K") (pinfunction "C_K") (pintype "passive"))
      (node (ref "U2") (pin "5") (pinfunction "D2_5") (pintype "output"))
    )
    (net (code "41") (name "IO11") (class "Default")
      (node (ref "CN2") (pin "7") (pinfunction "7_7") (pintype "passive"))
      (node (ref "LED10") (pin "K") (pinfunction "C_K") (pintype "passive"))
      (node (ref "U2") (pin "6") (pinfunction "D3_6") (pintype "output"))
    )
    (net (code "42") (name "IO12") (class "Default")
      (node (ref "CN2") (pin "9") (pinfunction "9_9") (pintype "passive"))
      (node (ref "LED11") (pin "K") (pinfunction "C_K") (pintype "passive"))
      (node (ref "U2") (pin "11") (pinfunction "D4_11") (pintype "output"))
    )
    (net (code "43") (name "IO13") (class "Default")
      (node (ref "CN2") (pin "11") (pinfunction "11_11") (pintype "passive"))
      (node (ref "LED12") (pin "K") (pinfunction "C_K") (pintype "passive"))
      (node (ref "U2") (pin "12") (pinfunction "D5_12") (pintype "output"))
    )
    (net (code "44") (name "IO14") (class "Default")
      (node (ref "LED39") (pin "K") (pinfunction "C_K") (pintype "passive"))
      (node (ref "U2") (pin "13") (pinfunction "D6_13") (pintype "output"))
    )
    (net (code "45") (name "IO15") (class "Default")
      (node (ref "LED40") (pin "K") (pinfunction "C_K") (pintype "passive"))
      (node (ref "U2") (pin "14") (pinfunction "D7_14") (pintype "output"))
    )
    (net (code "46") (name "IO16") (class "Default")
      (node (ref "CN3") (pin "1") (pinfunction "1_1") (pintype "passive"))
      (node (ref "LED13") (pin "K") (pinfunction "C_K") (pintype "passive"))
      (node (ref "U3") (pin "3") (pinfunction "D0_3") (pintype "output"))
    )
    (net (code "47") (name "IO17") (class "Default")
      (node (ref "CN3") (pin "3") (pinfunction "3_3") (pintype "passive"))
      (node (ref "LED14") (pin "K") (pinfunction "C_K") (pintype "passive"))
      (node (ref "U3") (pin "4") (pinfunction "D1_4") (pintype "output"))
    )
    (net (code "48") (name "IO18") (class "Default")
      (node (ref "CN3") (pin "5") (pinfunction "5_5") (pintype "passive"))
      (node (ref "LED15") (pin "K") (pinfunction "C_K") (pintype "passive"))
      (node (ref "U3") (pin "5") (pinfunction "D2_5") (pintype "output"))
    )
    (net (code "49") (name "IO19") (class "Default")
      (node (ref "CN3") (pin "7") (pinfunction "7_7") (pintype "passive"))
      (node (ref "LED16") (pin "K") (pinfunction "C_K") (pintype "passive"))
      (node (ref "U3") (pin "6") (pinfunction "D3_6") (pintype "output"))
    )
    (net (code "50") (name "IO20") (class "Default")
      (node (ref "CN3") (pin "9") (pinfunction "9_9") (pintype "passive"))
      (node (ref "LED17") (pin "K") (pinfunction "C_K") (pintype "passive"))
      (node (ref "U3") (pin "11") (pinfunction "D4_11") (pintype "output"))
    )
    (net (code "51") (name "IO21") (class "Default")
      (node (ref "CN3") (pin "11") (pinfunction "11_11") (pintype "passive"))
      (node (ref "LED18") (pin "K") (pinfunction "C_K") (pintype "passive"))
      (node (ref "U3") (pin "12") (pinfunction "D5_12") (pintype "output"))
    )
    (net (code "52") (name "IO22") (class "Default")
      (node (ref "LED41") (pin "K") (pinfunction "C_K") (pintype "passive"))
      (node (ref "U3") (pin "13") (pinfunction "D6_13") (pintype "output"))
    )
    (net (code "53") (name "IO23") (class "Default")
      (node (ref "LED42") (pin "K") (pinfunction "C_K") (pintype "passive"))
      (node (ref "U3") (pin "14") (pinfunction "D7_14") (pintype "output"))
    )
    (net (code "54") (name "IO24") (class "Default")
      (node (ref "CN4") (pin "1") (pinfunction "1_1") (pintype "passive"))
      (node (ref "LED19") (pin "K") (pinfunction "C_K") (pintype "passive"))
      (node (ref "U4") (pin "3") (pinfunction "D0_3") (pintype "output"))
    )
    (net (code "55") (name "IO25") (class "Default")
      (node (ref "CN4") (pin "3") (pinfunction "3_3") (pintype "passive"))
      (node (ref "LED20") (pin "K") (pinfunction "C_K") (pintype "passive"))
      (node (ref "U4") (pin "4") (pinfunction "D1_4") (pintype "output"))
    )
    (net (code "56") (name "IO26") (class "Default")
      (node (ref "CN4") (pin "5") (pinfunction "5_5") (pintype "passive"))
      (node (ref "LED21") (pin "K") (pinfunction "C_K") (pintype "passive"))
      (node (ref "U4") (pin "5") (pinfunction "D2_5") (pintype "output"))
    )
    (net (code "57") (name "IO27") (class "Default")
      (node (ref "CN4") (pin "7") (pinfunction "7_7") (pintype "passive"))
      (node (ref "LED22") (pin "K") (pinfunction "C_K") (pintype "passive"))
      (node (ref "U4") (pin "6") (pinfunction "D3_6") (pintype "output"))
    )
    (net (code "58") (name "IO28") (class "Default")
      (node (ref "CN4") (pin "9") (pinfunction "9_9") (pintype "passive"))
      (node (ref "LED23") (pin "K") (pinfunction "C_K") (pintype "passive"))
      (node (ref "U4") (pin "11") (pinfunction "D4_11") (pintype "output"))
    )
    (net (code "59") (name "IO29") (class "Default")
      (node (ref "CN4") (pin "11") (pinfunction "11_11") (pintype "passive"))
      (node (ref "LED24") (pin "K") (pinfunction "C_K") (pintype "passive"))
      (node (ref "U4") (pin "12") (pinfunction "D5_12") (pintype "output"))
    )
    (net (code "60") (name "IO30") (class "Default")
      (node (ref "LED43") (pin "K") (pinfunction "C_K") (pintype "passive"))
      (node (ref "U4") (pin "13") (pinfunction "D6_13") (pintype "output"))
    )
    (net (code "61") (name "IO31") (class "Default")
      (node (ref "LED44") (pin "K") (pinfunction "C_K") (pintype "passive"))
      (node (ref "U4") (pin "14") (pinfunction "D7_14") (pintype "output"))
    )
    (net (code "62") (name "IO32") (class "Default")
      (node (ref "CN5") (pin "1") (pinfunction "1_1") (pintype "passive"))
      (node (ref "LED25") (pin "K") (pinfunction "C_K") (pintype "passive"))
      (node (ref "U5") (pin "3") (pinfunction "D0_3") (pintype "output"))
    )
    (net (code "63") (name "IO33") (class "Default")
      (node (ref "CN5") (pin "3") (pinfunction "3_3") (pintype "passive"))
      (node (ref "LED26") (pin "K") (pinfunction "C_K") (pintype "passive"))
      (node (ref "U5") (pin "4") (pinfunction "D1_4") (pintype "output"))
    )
    (net (code "64") (name "IO34") (class "Default")
      (node (ref "CN5") (pin "5") (pinfunction "5_5") (pintype "passive"))
      (node (ref "LED27") (pin "K") (pinfunction "C_K") (pintype "passive"))
      (node (ref "U5") (pin "5") (pinfunction "D2_5") (pintype "output"))
    )
    (net (code "65") (name "IO35") (class "Default")
      (node (ref "CN5") (pin "7") (pinfunction "7_7") (pintype "passive"))
      (node (ref "LED28") (pin "K") (pinfunction "C_K") (pintype "passive"))
      (node (ref "U5") (pin "6") (pinfunction "D3_6") (pintype "output"))
    )
    (net (code "66") (name "IO36") (class "Default")
      (node (ref "CN5") (pin "9") (pinfunction "9_9") (pintype "passive"))
      (node (ref "LED29") (pin "K") (pinfunction "C_K") (pintype "passive"))
      (node (ref "U5") (pin "11") (pinfunction "D4_11") (pintype "output"))
    )
    (net (code "67") (name "IO37") (class "Default")
      (node (ref "CN5") (pin "11") (pinfunction "11_11") (pintype "passive"))
      (node (ref "LED30") (pin "K") (pinfunction "C_K") (pintype "passive"))
      (node (ref "U5") (pin "12") (pinfunction "D5_12") (pintype "output"))
    )
    (net (code "68") (name "IO38") (class "Default")
      (node (ref "LED45") (pin "K") (pinfunction "C_K") (pintype "passive"))
      (node (ref "U5") (pin "13") (pinfunction "D6_13") (pintype "output"))
    )
    (net (code "69") (name "IO39") (class "Default")
      (node (ref "LED46") (pin "K") (pinfunction "C_K") (pintype "passive"))
      (node (ref "U5") (pin "14") (pinfunction "D7_14") (pintype "output"))
    )
    (net (code "70") (name "IO40") (class "Default")
      (node (ref "CN6") (pin "1") (pinfunction "1_1") (pintype "passive"))
      (node (ref "LED31") (pin "K") (pinfunction "C_K") (pintype "passive"))
      (node (ref "U6") (pin "3") (pinfunction "D0_3") (pintype "output"))
    )
    (net (code "71") (name "IO41") (class "Default")
      (node (ref "CN6") (pin "3") (pinfunction "3_3") (pintype "passive"))
      (node (ref "LED32") (pin "K") (pinfunction "C_K") (pintype "passive"))
      (node (ref "U6") (pin "4") (pinfunction "D1_4") (pintype "output"))
    )
    (net (code "72") (name "IO42") (class "Default")
      (node (ref "CN6") (pin "5") (pinfunction "5_5") (pintype "passive"))
      (node (ref "LED33") (pin "K") (pinfunction "C_K") (pintype "passive"))
      (node (ref "U6") (pin "5") (pinfunction "D2_5") (pintype "output"))
    )
    (net (code "73") (name "IO43") (class "Default")
      (node (ref "CN6") (pin "7") (pinfunction "7_7") (pintype "passive"))
      (node (ref "LED34") (pin "K") (pinfunction "C_K") (pintype "passive"))
      (node (ref "U6") (pin "6") (pinfunction "D3_6") (pintype "output"))
    )
    (net (code "74") (name "IO44") (class "Default")
      (node (ref "CN6") (pin "9") (pinfunction "9_9") (pintype "passive"))
      (node (ref "LED35") (pin "K") (pinfunction "C_K") (pintype "passive"))
      (node (ref "U6") (pin "11") (pinfunction "D4_11") (pintype "output"))
    )
    (net (code "75") (name "IO45") (class "Default")
      (node (ref "CN6") (pin "11") (pinfunction "11_11") (pintype "passive"))
      (node (ref "LED36") (pin "K") (pinfunction "C_K") (pintype "passive"))
      (node (ref "U6") (pin "12") (pinfunction "D5_12") (pintype "output"))
    )
    (net (code "76") (name "IO46") (class "Default")
      (node (ref "LED47") (pin "K") (pinfunction "C_K") (pintype "passive"))
      (node (ref "U6") (pin "13") (pinfunction "D6_13") (pintype "output"))
    )
    (net (code "77") (name "IO47") (class "Default")
      (node (ref "LED48") (pin "K") (pinfunction "C_K") (pintype "passive"))
      (node (ref "U6") (pin "14") (pinfunction "D7_14") (pintype "output"))
    )
    (net (code "78") (name "LATCH") (class "Default")
      (node (ref "CN7") (pin "10") (pinfunction "10_10") (pintype "passive"))
      (node (ref "CN8") (pin "10") (pinfunction "10_10") (pintype "passive"))
      (node (ref "TP12") (pin "P$1") (pinfunction "1_P$1") (pintype "bidirectional"))
      (node (ref "U1") (pin "10") (pinfunction "RCK_10") (pintype "input"))
      (node (ref "U2") (pin "10") (pinfunction "RCK_10") (pintype "input"))
      (node (ref "U3") (pin "10") (pinfunction "RCK_10") (pintype "input"))
      (node (ref "U4") (pin "10") (pinfunction "RCK_10") (pintype "input"))
      (node (ref "U5") (pin "10") (pinfunction "RCK_10") (pintype "input"))
      (node (ref "U6") (pin "10") (pinfunction "RCK_10") (pintype "input"))
    )
    (net (code "79") (name "Net-(LED1-PadA)") (class "Default")
      (node (ref "LED1") (pin "A") (pinfunction "A_A") (pintype "passive"))
      (node (ref "R1") (pin "1") (pinfunction "1_1") (pintype "passive"))
    )
    (net (code "80") (name "Net-(LED2-PadA)") (class "Default")
      (node (ref "LED2") (pin "A") (pinfunction "A_A") (pintype "passive"))
      (node (ref "R2") (pin "1") (pinfunction "1_1") (pintype "passive"))
    )
    (net (code "81") (name "Net-(LED3-PadA)") (class "Default")
      (node (ref "LED3") (pin "A") (pinfunction "A_A") (pintype "passive"))
      (node (ref "R3") (pin "1") (pinfunction "1_1") (pintype "passive"))
    )
    (net (code "82") (name "Net-(LED4-PadA)") (class "Default")
      (node (ref "LED4") (pin "A") (pinfunction "A_A") (pintype "passive"))
      (node (ref "R4") (pin "1") (pinfunction "1_1") (pintype "passive"))
    )
    (net (code "83") (name "Net-(LED5-PadA)") (class "Default")
      (node (ref "LED5") (pin "A") (pinfunction "A_A") (pintype "passive"))
      (node (ref "R5") (pin "1") (pinfunction "1_1") (pintype "passive"))
    )
    (net (code "84") (name "Net-(LED6-PadA)") (class "Default")
      (node (ref "LED6") (pin "A") (pinfunction "A_A") (pintype "passive"))
      (node (ref "R6") (pin "1") (pinfunction "1_1") (pintype "passive"))
    )
    (net (code "85") (name "Net-(LED7-PadA)") (class "Default")
      (node (ref "LED7") (pin "A") (pinfunction "A_A") (pintype "passive"))
      (node (ref "R9") (pin "1") (pinfunction "1_1") (pintype "passive"))
    )
    (net (code "86") (name "Net-(LED8-PadA)") (class "Default")
      (node (ref "LED8") (pin "A") (pinfunction "A_A") (pintype "passive"))
      (node (ref "R10") (pin "1") (pinfunction "1_1") (pintype "passive"))
    )
    (net (code "87") (name "Net-(LED9-PadA)") (class "Default")
      (node (ref "LED9") (pin "A") (pinfunction "A_A") (pintype "passive"))
      (node (ref "R11") (pin "1") (pinfunction "1_1") (pintype "passive"))
    )
    (net (code "88") (name "Net-(LED10-PadA)") (class "Default")
      (node (ref "LED10") (pin "A") (pinfunction "A_A") (pintype "passive"))
      (node (ref "R12") (pin "1") (pinfunction "1_1") (pintype "passive"))
    )
    (net (code "89") (name "Net-(LED11-PadA)") (class "Default")
      (node (ref "LED11") (pin "A") (pinfunction "A_A") (pintype "passive"))
      (node (ref "R13") (pin "1") (pinfunction "1_1") (pintype "passive"))
    )
    (net (code "90") (name "Net-(LED12-PadA)") (class "Default")
      (node (ref "LED12") (pin "A") (pinfunction "A_A") (pintype "passive"))
      (node (ref "R14") (pin "1") (pinfunction "1_1") (pintype "passive"))
    )
    (net (code "91") (name "Net-(LED13-PadA)") (class "Default")
      (node (ref "LED13") (pin "A") (pinfunction "A_A") (pintype "passive"))
      (node (ref "R17") (pin "1") (pinfunction "1_1") (pintype "passive"))
    )
    (net (code "92") (name "Net-(LED14-PadA)") (class "Default")
      (node (ref "LED14") (pin "A") (pinfunction "A_A") (pintype "passive"))
      (node (ref "R18") (pin "1") (pinfunction "1_1") (pintype "passive"))
    )
    (net (code "93") (name "Net-(LED15-PadA)") (class "Default")
      (node (ref "LED15") (pin "A") (pinfunction "A_A") (pintype "passive"))
      (node (ref "R19") (pin "1") (pinfunction "1_1") (pintype "passive"))
    )
    (net (code "94") (name "Net-(LED16-PadA)") (class "Default")
      (node (ref "LED16") (pin "A") (pinfunction "A_A") (pintype "passive"))
      (node (ref "R20") (pin "1") (pinfunction "1_1") (pintype "passive"))
    )
    (net (code "95") (name "Net-(LED17-PadA)") (class "Default")
      (node (ref "LED17") (pin "A") (pinfunction "A_A") (pintype "passive"))
      (node (ref "R21") (pin "1") (pinfunction "1_1") (pintype "passive"))
    )
    (net (code "96") (name "Net-(LED18-PadA)") (class "Default")
      (node (ref "LED18") (pin "A") (pinfunction "A_A") (pintype "passive"))
      (node (ref "R22") (pin "1") (pinfunction "1_1") (pintype "passive"))
    )
    (net (code "97") (name "Net-(LED19-PadA)") (class "Default")
      (node (ref "LED19") (pin "A") (pinfunction "A_A") (pintype "passive"))
      (node (ref "R25") (pin "1") (pinfunction "1_1") (pintype "passive"))
    )
    (net (code "98") (name "Net-(LED20-PadA)") (class "Default")
      (node (ref "LED20") (pin "A") (pinfunction "A_A") (pintype "passive"))
      (node (ref "R26") (pin "1") (pinfunction "1_1") (pintype "passive"))
    )
    (net (code "99") (name "Net-(LED21-PadA)") (class "Default")
      (node (ref "LED21") (pin "A") (pinfunction "A_A") (pintype "passive"))
      (node (ref "R27") (pin "1") (pinfunction "1_1") (pintype "passive"))
    )
    (net (code "100") (name "Net-(LED22-PadA)") (class "Default")
      (node (ref "LED22") (pin "A") (pinfunction "A_A") (pintype "passive"))
      (node (ref "R28") (pin "1") (pinfunction "1_1") (pintype "passive"))
    )
    (net (code "101") (name "Net-(LED23-PadA)") (class "Default")
      (node (ref "LED23") (pin "A") (pinfunction "A_A") (pintype "passive"))
      (node (ref "R29") (pin "1") (pinfunction "1_1") (pintype "passive"))
    )
    (net (code "102") (name "Net-(LED24-PadA)") (class "Default")
      (node (ref "LED24") (pin "A") (pinfunction "A_A") (pintype "passive"))
      (node (ref "R30") (pin "1") (pinfunction "1_1") (pintype "passive"))
    )
    (net (code "103") (name "Net-(LED25-PadA)") (class "Default")
      (node (ref "LED25") (pin "A") (pinfunction "A_A") (pintype "passive"))
      (node (ref "R33") (pin "1") (pinfunction "1_1") (pintype "passive"))
    )
    (net (code "104") (name "Net-(LED26-PadA)") (class "Default")
      (node (ref "LED26") (pin "A") (pinfunction "A_A") (pintype "passive"))
      (node (ref "R34") (pin "1") (pinfunction "1_1") (pintype "passive"))
    )
    (net (code "105") (name "Net-(LED27-PadA)") (class "Default")
      (node (ref "LED27") (pin "A") (pinfunction "A_A") (pintype "passive"))
      (node (ref "R35") (pin "1") (pinfunction "1_1") (pintype "passive"))
    )
    (net (code "106") (name "Net-(LED28-PadA)") (class "Default")
      (node (ref "LED28") (pin "A") (pinfunction "A_A") (pintype "passive"))
      (node (ref "R36") (pin "1") (pinfunction "1_1") (pintype "passive"))
    )
    (net (code "107") (name "Net-(LED29-PadA)") (class "Default")
      (node (ref "LED29") (pin "A") (pinfunction "A_A") (pintype "passive"))
      (node (ref "R37") (pin "1") (pinfunction "1_1") (pintype "passive"))
    )
    (net (code "108") (name "Net-(LED30-PadA)") (class "Default")
      (node (ref "LED30") (pin "A") (pinfunction "A_A") (pintype "passive"))
      (node (ref "R38") (pin "1") (pinfunction "1_1") (pintype "passive"))
    )
    (net (code "109") (name "Net-(LED31-PadA)") (class "Default")
      (node (ref "LED31") (pin "A") (pinfunction "A_A") (pintype "passive"))
      (node (ref "R41") (pin "1") (pinfunction "1_1") (pintype "passive"))
    )
    (net (code "110") (name "Net-(LED32-PadA)") (class "Default")
      (node (ref "LED32") (pin "A") (pinfunction "A_A") (pintype "passive"))
      (node (ref "R42") (pin "1") (pinfunction "1_1") (pintype "passive"))
    )
    (net (code "111") (name "Net-(LED33-PadA)") (class "Default")
      (node (ref "LED33") (pin "A") (pinfunction "A_A") (pintype "passive"))
      (node (ref "R43") (pin "1") (pinfunction "1_1") (pintype "passive"))
    )
    (net (code "112") (name "Net-(LED34-PadA)") (class "Default")
      (node (ref "LED34") (pin "A") (pinfunction "A_A") (pintype "passive"))
      (node (ref "R44") (pin "1") (pinfunction "1_1") (pintype "passive"))
    )
    (net (code "113") (name "Net-(LED35-PadA)") (class "Default")
      (node (ref "LED35") (pin "A") (pinfunction "A_A") (pintype "passive"))
      (node (ref "R45") (pin "1") (pinfunction "1_1") (pintype "passive"))
    )
    (net (code "114") (name "Net-(LED36-PadA)") (class "Default")
      (node (ref "LED36") (pin "A") (pinfunction "A_A") (pintype "passive"))
      (node (ref "R46") (pin "1") (pinfunction "1_1") (pintype "passive"))
    )
    (net (code "115") (name "Net-(LED37-PadA)") (class "Default")
      (node (ref "LED37") (pin "A") (pinfunction "A_A") (pintype "passive"))
      (node (ref "R7") (pin "1") (pinfunction "1_1") (pintype "passive"))
    )
    (net (code "116") (name "Net-(LED38-PadA)") (class "Default")
      (node (ref "LED38") (pin "A") (pinfunction "A_A") (pintype "passive"))
      (node (ref "R8") (pin "1") (pinfunction "1_1") (pintype "passive"))
    )
    (net (code "117") (name "Net-(LED39-PadA)") (class "Default")
      (node (ref "LED39") (pin "A") (pinfunction "A_A") (pintype "passive"))
      (node (ref "R15") (pin "1") (pinfunction "1_1") (pintype "passive"))
    )
    (net (code "118") (name "Net-(LED40-PadA)") (class "Default")
      (node (ref "LED40") (pin "A") (pinfunction "A_A") (pintype "passive"))
      (node (ref "R16") (pin "1") (pinfunction "1_1") (pintype "passive"))
    )
    (net (code "119") (name "Net-(LED41-PadA)") (class "Default")
      (node (ref "LED41") (pin "A") (pinfunction "A_A") (pintype "passive"))
      (node (ref "R23") (pin "1") (pinfunction "1_1") (pintype "passive"))
    )
    (net (code "120") (name "Net-(LED42-PadA)") (class "Default")
      (node (ref "LED42") (pin "A") (pinfunction "A_A") (pintype "passive"))
      (node (ref "R24") (pin "1") (pinfunction "1_1") (pintype "passive"))
    )
    (net (code "121") (name "Net-(LED43-PadA)") (class "Default")
      (node (ref "LED43") (pin "A") (pinfunction "A_A") (pintype "passive"))
      (node (ref "R31") (pin "1") (pinfunction "1_1") (pintype "passive"))
    )
    (net (code "122") (name "Net-(LED44-PadA)") (class "Default")
      (node (ref "LED44") (pin "A") (pinfunction "A_A") (pintype "passive"))
      (node (ref "R32") (pin "1") (pinfunction "1_1") (pintype "passive"))
    )
    (net (code "123") (name "Net-(LED45-PadA)") (class "Default")
      (node (ref "LED45") (pin "A") (pinfunction "A_A") (pintype "passive"))
      (node (ref "R39") (pin "1") (pinfunction "1_1") (pintype "passive"))
    )
    (net (code "124") (name "Net-(LED46-PadA)") (class "Default")
      (node (ref "LED46") (pin "A") (pinfunction "A_A") (pintype "passive"))
      (node (ref "R40") (pin "1") (pinfunction "1_1") (pintype "passive"))
    )
    (net (code "125") (name "Net-(LED47-PadA)") (class "Default")
      (node (ref "LED47") (pin "A") (pinfunction "A_A") (pintype "passive"))
      (node (ref "R47") (pin "1") (pinfunction "1_1") (pintype "passive"))
    )
    (net (code "126") (name "Net-(LED48-PadA)") (class "Default")
      (node (ref "LED48") (pin "A") (pinfunction "A_A") (pintype "passive"))
      (node (ref "R48") (pin "1") (pinfunction "1_1") (pintype "passive"))
    )
    (net (code "127") (name "Net-(LED49-PadA)") (class "Default")
      (node (ref "LED49") (pin "A") (pinfunction "A_A") (pintype "passive"))
      (node (ref "R49") (pin "1") (pinfunction "1_1") (pintype "passive"))
    )
    (net (code "128") (name "unconnected-(CN8-Pad3)") (class "Default")
      (node (ref "CN8") (pin "3") (pinfunction "3_3") (pintype "passive"))
    )
  )
)
